# Antena_RF.net
KiCad netlist of a schematic drawn in Altium Designer
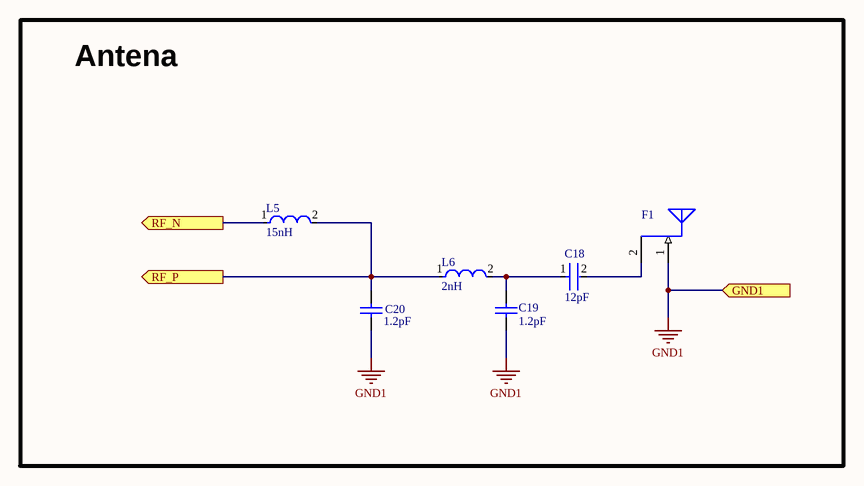
[diagram p0: Antena RF.SchDoc]

(export (version "E")
  (design (tool "Eeschema 10.0.6"))
  (components
    (comp (ref "C18")
      (value "12pF")
      (footprint "FP-C0603C-CF-MFG")
      (description "CAP CER 12PF 50V NP0 0603")
      (fields (field (name "MANUFACTURER") "KEMET") (field (name "TOLERANCE") "0.5 pF"))
      (libsource (lib "Altium Content Vault") (part "b4654b650e69147ec39a6b967a45e02"))
    )
    (comp (ref "C19")
      (value "1.2pF")
      (footprint "CAPC1005X55X25ML05T10")
      (fields (field (name "MANUFACTURER") "Murata") (field (name "PART NUMBER") "GRM1555C1H1R2BA01D"))
      (libsource (lib "Altium Content Vault") (part "CAP"))
    )
    (comp (ref "C20")
      (value "1.2pF")
      (footprint "CAPC1005X55X25ML05T10")
      (fields (field (name "MANUFACTURER") "Murata") (field (name "PART NUMBER") "GRM1555C1H1R2BA01D"))
      (libsource (lib "Altium Content Vault") (part "CAP"))
    )
    (comp (ref "F1") (value "-") (footprint "PCBAntenna") (libsource (lib "DEOP2021") (part "PCBAntenna")))
    (comp (ref "L5")
      (value "15nH")
      (footprint "FP-LQW15AN_00-W0_6-0_1-MFG")
      (description "Wire Wound RF Inductor 15nH ±5% 460mA 0.16Ω 0402 (1005)")
      (fields (field (name "TOLERANCE") "5%"))
      (libsource (lib "Altium Content Vault") (part "725321dda6339637d4d059423bc1c3c"))
    )
    (comp (ref "L6")
      (value "2nH")
      (footprint "FP-LQW15AN_00-W0_6-0_1-MFG")
      (description "Wire Wound RF Inductor 2.4nH ±0.1nH 850mA 0.05Ω 0402 (1005)")
      (fields (field (name "TOLERANCE") "2%"))
      (libsource (lib "Altium Content Vault") (part "725321dda6339637d4d059423bc1c3c"))
    )
  )
  (nets
    (net (code "1") (name "/RF_N") (class "Default")
      (node (ref "L5") (pin "1") (pinfunction "1_1") (pintype "passive"))
    )
    (net (code "2") (name "/RF_P") (class "Default")
      (node (ref "C20") (pin "2") (pinfunction "2_2") (pintype "passive"))
      (node (ref "L5") (pin "2") (pinfunction "2_2") (pintype "passive"))
      (node (ref "L6") (pin "1") (pinfunction "1_1") (pintype "passive"))
    )
    (net (code "3") (name "GND1") (class "Default")
      (node (ref "C19") (pin "1") (pinfunction "1_1") (pintype "passive"))
      (node (ref "C20") (pin "1") (pinfunction "1_1") (pintype "passive"))
      (node (ref "F1") (pin "1") (pinfunction "FeedPoint_1") (pintype "input"))
    )
    (net (code "4") (name "Net-(C18-Pad1)") (class "Default")
      (node (ref "C18") (pin "1") (pinfunction "1_1") (pintype "passive"))
      (node (ref "C19") (pin "2") (pinfunction "2_2") (pintype "passive"))
      (node (ref "L6") (pin "2") (pinfunction "2_2") (pintype "passive"))
    )
    (net (code "5") (name "Net-(F1-GND)") (class "Default")
      (node (ref "C18") (pin "2") (pinfunction "2_2") (pintype "passive"))
      (node (ref "F1") (pin "2") (pinfunction "GND_2") (pintype "power_in"))
    )
  )
)
